# Communication_sheet.net
KiCad netlist of a schematic drawn in Altium Designer
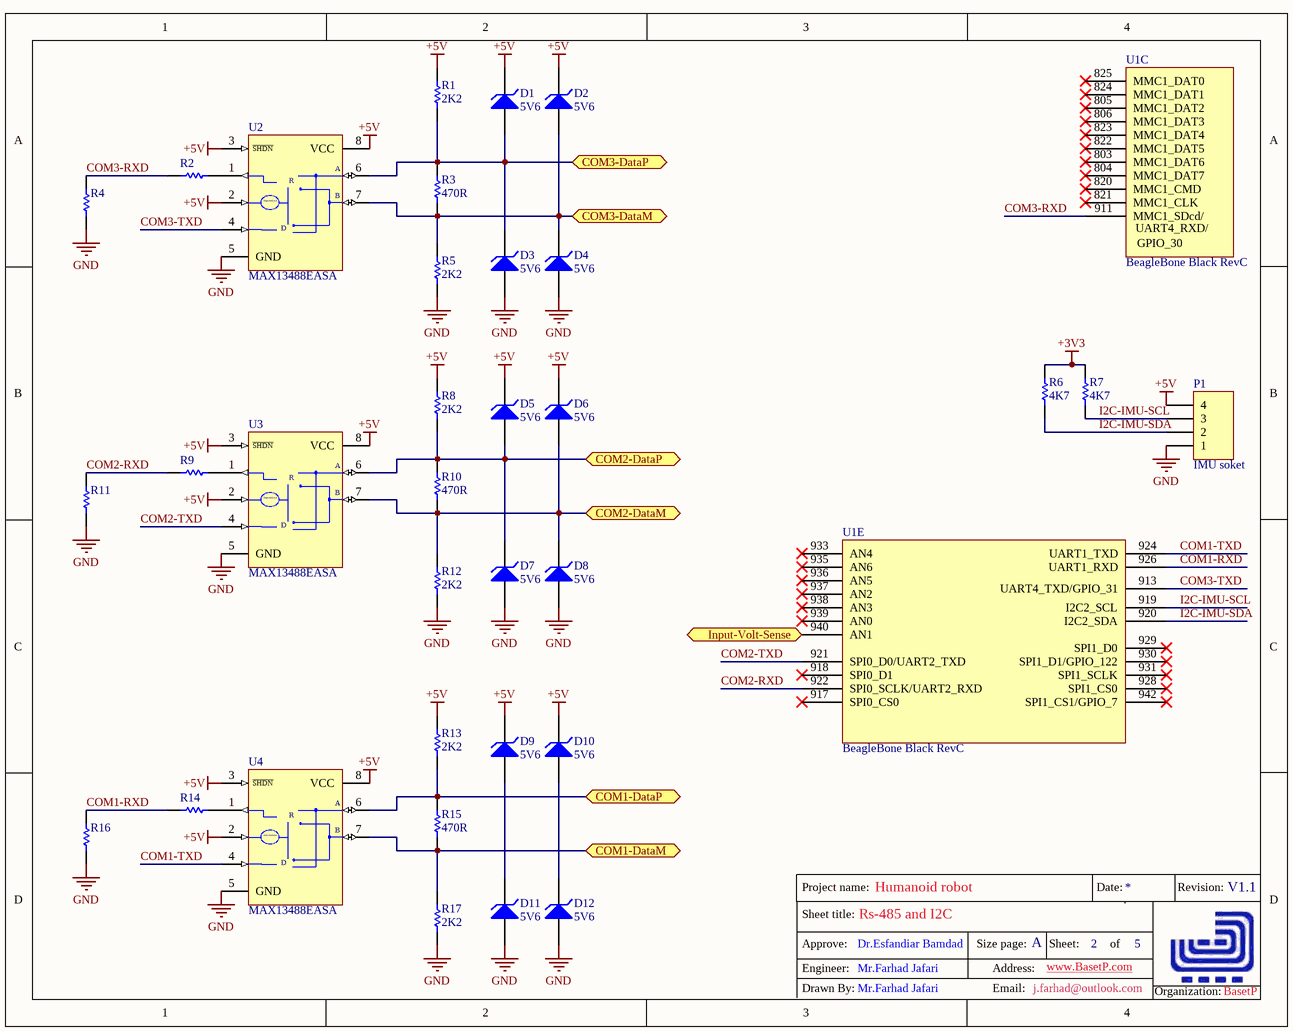
[diagram p0: Communication sheet.SchDoc]

(export (version "E")
  (design (tool "Eeschema 10.0.6"))
  (components
    (comp (ref "D1")
      (value "5V6")
      (footprint "diode-0.4")
      (description "Zener Diode")
      (fields (field (name "PUBLISHER") "Altium Limited"))
      (libsource (lib "Farhad") (part "D Zener"))
    )
    (comp (ref "D2")
      (value "5V6")
      (footprint "diode-0.4")
      (description "Zener Diode")
      (fields (field (name "PUBLISHER") "Altium Limited"))
      (libsource (lib "Farhad") (part "D Zener"))
    )
    (comp (ref "D3")
      (value "5V6")
      (footprint "diode-0.4")
      (description "Zener Diode")
      (fields (field (name "PUBLISHER") "Altium Limited"))
      (libsource (lib "Farhad") (part "D Zener"))
    )
    (comp (ref "D4")
      (value "5V6")
      (footprint "diode-0.4")
      (description "Zener Diode")
      (fields (field (name "PUBLISHER") "Altium Limited"))
      (libsource (lib "Farhad") (part "D Zener"))
    )
    (comp (ref "D5")
      (value "5V6")
      (footprint "diode-0.4")
      (description "Zener Diode")
      (fields (field (name "PUBLISHER") "Altium Limited"))
      (libsource (lib "Farhad") (part "D Zener"))
    )
    (comp (ref "D6")
      (value "5V6")
      (footprint "diode-0.4")
      (description "Zener Diode")
      (fields (field (name "PUBLISHER") "Altium Limited"))
      (libsource (lib "Farhad") (part "D Zener"))
    )
    (comp (ref "D7")
      (value "5V6")
      (footprint "diode-0.4")
      (description "Zener Diode")
      (fields (field (name "PUBLISHER") "Altium Limited"))
      (libsource (lib "Farhad") (part "D Zener"))
    )
    (comp (ref "D8")
      (value "5V6")
      (footprint "diode-0.4")
      (description "Zener Diode")
      (fields (field (name "PUBLISHER") "Altium Limited"))
      (libsource (lib "Farhad") (part "D Zener"))
    )
    (comp (ref "D9")
      (value "5V6")
      (footprint "diode-0.4")
      (description "Zener Diode")
      (fields (field (name "PUBLISHER") "Altium Limited"))
      (libsource (lib "Farhad") (part "D Zener"))
    )
    (comp (ref "D10")
      (value "5V6")
      (footprint "diode-0.4")
      (description "Zener Diode")
      (fields (field (name "PUBLISHER") "Altium Limited"))
      (libsource (lib "Farhad") (part "D Zener"))
    )
    (comp (ref "D11")
      (value "5V6")
      (footprint "diode-0.4")
      (description "Zener Diode")
      (fields (field (name "PUBLISHER") "Altium Limited"))
      (libsource (lib "Farhad") (part "D Zener"))
    )
    (comp (ref "D12")
      (value "5V6")
      (footprint "diode-0.4")
      (description "Zener Diode")
      (fields (field (name "PUBLISHER") "Altium Limited"))
      (libsource (lib "Farhad") (part "D Zener"))
    )
    (comp (ref "P1")
      (value "IMU soket")
      (footprint "HDR1X4")
      (description "Header, 4-Pin")
      (fields (field (name "PUBLISHER") "Altium Limited"))
      (libsource (lib "Farhad_Library") (part "Header 4"))
    )
    (comp (ref "R1")
      (value "2K2")
      (footprint "6-0805")
      (fields (field (name "PUBLISHER") "Altium Limited"))
      (libsource (lib "Panasonic Resistor") (part "ERJ6RS"))
    )
    (comp (ref "R2")
      (value "620")
      (footprint "6-0805")
      (fields (field (name "PUBLISHER") "Altium Limited"))
      (libsource (lib "Panasonic Resistor") (part "ERJ6RS"))
    )
    (comp (ref "R3")
      (value "470R")
      (footprint "6-0805")
      (fields (field (name "PUBLISHER") "Altium Limited"))
      (libsource (lib "Panasonic Resistor") (part "ERJ6RS"))
    )
    (comp (ref "R4")
      (value "1K")
      (footprint "6-0805")
      (fields (field (name "PUBLISHER") "Altium Limited"))
      (libsource (lib "Panasonic Resistor") (part "ERJ6RS"))
    )
    (comp (ref "R5")
      (value "2K2")
      (footprint "6-0805")
      (fields (field (name "PUBLISHER") "Altium Limited"))
      (libsource (lib "Panasonic Resistor") (part "ERJ6RS"))
    )
    (comp (ref "R6")
      (value "4K7")
      (footprint "6-0805")
      (fields (field (name "PUBLISHER") "Altium Limited"))
      (libsource (lib "Panasonic Resistor") (part "ERJ6RS"))
    )
    (comp (ref "R7")
      (value "4K7")
      (footprint "6-0805")
      (fields (field (name "PUBLISHER") "Altium Limited"))
      (libsource (lib "Panasonic Resistor") (part "ERJ6RS"))
    )
    (comp (ref "R8")
      (value "2K2")
      (footprint "6-0805")
      (fields (field (name "PUBLISHER") "Altium Limited"))
      (libsource (lib "Panasonic Resistor") (part "ERJ6RS"))
    )
    (comp (ref "R9")
      (value "680R")
      (footprint "6-0805")
      (fields (field (name "PUBLISHER") "Altium Limited"))
      (libsource (lib "Panasonic Resistor") (part "ERJ6RS"))
    )
    (comp (ref "R10")
      (value "470R")
      (footprint "6-0805")
      (fields (field (name "PUBLISHER") "Altium Limited"))
      (libsource (lib "Panasonic Resistor") (part "ERJ6RS"))
    )
    (comp (ref "R11")
      (value "1K")
      (footprint "6-0805")
      (fields (field (name "PUBLISHER") "Altium Limited"))
      (libsource (lib "Panasonic Resistor") (part "ERJ6RS"))
    )
    (comp (ref "R12")
      (value "2K2")
      (footprint "6-0805")
      (fields (field (name "PUBLISHER") "Altium Limited"))
      (libsource (lib "Panasonic Resistor") (part "ERJ6RS"))
    )
    (comp (ref "R13")
      (value "2K2")
      (footprint "6-0805")
      (fields (field (name "PUBLISHER") "Altium Limited"))
      (libsource (lib "Panasonic Resistor") (part "ERJ6RS"))
    )
    (comp (ref "R14")
      (value "680R")
      (footprint "6-0805")
      (fields (field (name "PUBLISHER") "Altium Limited"))
      (libsource (lib "Panasonic Resistor") (part "ERJ6RS"))
    )
    (comp (ref "R15")
      (value "470R")
      (footprint "6-0805")
      (fields (field (name "PUBLISHER") "Altium Limited"))
      (libsource (lib "Panasonic Resistor") (part "ERJ6RS"))
    )
    (comp (ref "R16")
      (value "1K")
      (footprint "6-0805")
      (fields (field (name "PUBLISHER") "Altium Limited"))
      (libsource (lib "Panasonic Resistor") (part "ERJ6RS"))
    )
    (comp (ref "R17")
      (value "2K2")
      (footprint "6-0805")
      (fields (field (name "PUBLISHER") "Altium Limited"))
      (libsource (lib "Panasonic Resistor") (part "ERJ6RS"))
    )
    (comp (ref "U1")
      (value "BeagleBone Black RevC")
      (footprint "BBB-C")
      (libsource (lib "Farhad_Library") (part "BeagleBoneBlackRevC"))
    )
    (comp (ref "U2")
      (value "MAX13488EASA")
      (footprint "NSO8_N")
      (description "Low-Power,  RS-485/RS-422 Transceiver, Auto direciton")
      (fields (field (name "PUBLISHER") "Farhad Jafari"))
      (libsource (lib "Farhad_Library") (part "MAX13488EASA"))
    )
    (comp (ref "U3")
      (value "MAX13488EASA")
      (footprint "NSO8_N")
      (description "Low-Power,  RS-485/RS-422 Transceiver, Auto direciton")
      (fields (field (name "PUBLISHER") "Farhad Jafari"))
      (libsource (lib "Farhad_Library") (part "MAX13488EASA"))
    )
    (comp (ref "U4")
      (value "MAX13488EASA")
      (footprint "NSO8_N")
      (description "Low-Power,  RS-485/RS-422 Transceiver, Auto direciton")
      (fields (field (name "PUBLISHER") "Farhad Jafari"))
      (libsource (lib "Farhad_Library") (part "MAX13488EASA"))
    )
  )
  (nets
    (net (code "1") (name "+3V3") (class "Default")
      (node (ref "R6") (pin "1") (pinfunction "1_1") (pintype "passive"))
      (node (ref "R7") (pin "1") (pinfunction "1_1") (pintype "passive"))
    )
    (net (code "2") (name "+5V") (class "Default")
      (node (ref "D1") (pin "2") (pinfunction "K_2") (pintype "passive"))
      (node (ref "D10") (pin "2") (pinfunction "K_2") (pintype "passive"))
      (node (ref "D2") (pin "2") (pinfunction "K_2") (pintype "passive"))
      (node (ref "D5") (pin "2") (pinfunction "K_2") (pintype "passive"))
      (node (ref "D6") (pin "2") (pinfunction "K_2") (pintype "passive"))
      (node (ref "D9") (pin "2") (pinfunction "K_2") (pintype "passive"))
      (node (ref "P1") (pin "4") (pinfunction "4_4") (pintype "passive"))
      (node (ref "R1") (pin "1") (pinfunction "1_1") (pintype "passive"))
      (node (ref "R13") (pin "1") (pinfunction "1_1") (pintype "passive"))
      (node (ref "R8") (pin "1") (pinfunction "1_1") (pintype "passive"))
      (node (ref "U2") (pin "2") (pinfunction "~{RE}_2") (pintype "input"))
      (node (ref "U2") (pin "3") (pinfunction "~{SHDN}_3") (pintype "input"))
      (node (ref "U2") (pin "8") (pinfunction "VCC_8") (pintype "power_in"))
      (node (ref "U3") (pin "2") (pinfunction "~{RE}_2") (pintype "input"))
      (node (ref "U3") (pin "3") (pinfunction "~{SHDN}_3") (pintype "input"))
      (node (ref "U3") (pin "8") (pinfunction "VCC_8") (pintype "power_in"))
      (node (ref "U4") (pin "2") (pinfunction "~{RE}_2") (pintype "input"))
      (node (ref "U4") (pin "3") (pinfunction "~{SHDN}_3") (pintype "input"))
      (node (ref "U4") (pin "8") (pinfunction "VCC_8") (pintype "power_in"))
    )
    (net (code "3") (name "/COM1-DataM") (class "Default")
      (node (ref "R15") (pin "2") (pinfunction "2_2") (pintype "passive"))
      (node (ref "R17") (pin "1") (pinfunction "1_1") (pintype "passive"))
      (node (ref "U4") (pin "7") (pinfunction "B_7") (pintype "bidirectional"))
    )
    (net (code "4") (name "/COM1-DataP") (class "Default")
      (node (ref "R13") (pin "2") (pinfunction "2_2") (pintype "passive"))
      (node (ref "R15") (pin "1") (pinfunction "1_1") (pintype "passive"))
      (node (ref "U4") (pin "6") (pinfunction "A_6") (pintype "bidirectional"))
    )
    (net (code "5") (name "/COM1-RXD") (class "Default")
      (node (ref "R14") (pin "1") (pinfunction "1_1") (pintype "passive"))
      (node (ref "R16") (pin "2") (pinfunction "2_2") (pintype "passive"))
      (node (ref "U1") (pin "926") (pinfunction "UART1_RXD_926") (pintype "passive"))
    )
    (net (code "6") (name "/COM1-TXD") (class "Default")
      (node (ref "U1") (pin "924") (pinfunction "UART1_TXD_924") (pintype "passive"))
      (node (ref "U4") (pin "4") (pinfunction "DI_4") (pintype "input"))
    )
    (net (code "7") (name "/COM2-DataM") (class "Default")
      (node (ref "D6") (pin "1") (pinfunction "A_1") (pintype "passive"))
      (node (ref "D8") (pin "2") (pinfunction "K_2") (pintype "passive"))
      (node (ref "R10") (pin "2") (pinfunction "2_2") (pintype "passive"))
      (node (ref "R12") (pin "1") (pinfunction "1_1") (pintype "passive"))
      (node (ref "U3") (pin "7") (pinfunction "B_7") (pintype "bidirectional"))
    )
    (net (code "8") (name "/COM2-DataP") (class "Default")
      (node (ref "D5") (pin "1") (pinfunction "A_1") (pintype "passive"))
      (node (ref "D7") (pin "2") (pinfunction "K_2") (pintype "passive"))
      (node (ref "R10") (pin "1") (pinfunction "1_1") (pintype "passive"))
      (node (ref "R8") (pin "2") (pinfunction "2_2") (pintype "passive"))
      (node (ref "U3") (pin "6") (pinfunction "A_6") (pintype "bidirectional"))
    )
    (net (code "9") (name "/COM2-RXD") (class "Default")
      (node (ref "R11") (pin "1") (pinfunction "1_1") (pintype "passive"))
      (node (ref "R9") (pin "2") (pinfunction "2_2") (pintype "passive"))
      (node (ref "U1") (pin "922") (pinfunction "SPI0_SCLK/UART2_RXD_922") (pintype "passive"))
    )
    (net (code "10") (name "/COM2-TXD") (class "Default")
      (node (ref "U1") (pin "921") (pinfunction "SPI0_D0/UART2_TXD_921") (pintype "passive"))
      (node (ref "U3") (pin "4") (pinfunction "DI_4") (pintype "input"))
    )
    (net (code "11") (name "/COM3-DataM") (class "Default")
      (node (ref "D2") (pin "1") (pinfunction "A_1") (pintype "passive"))
      (node (ref "D4") (pin "2") (pinfunction "K_2") (pintype "passive"))
      (node (ref "R3") (pin "2") (pinfunction "2_2") (pintype "passive"))
      (node (ref "R5") (pin "1") (pinfunction "1_1") (pintype "passive"))
      (node (ref "U2") (pin "7") (pinfunction "B_7") (pintype "bidirectional"))
    )
    (net (code "12") (name "/COM3-DataP") (class "Default")
      (node (ref "D1") (pin "1") (pinfunction "A_1") (pintype "passive"))
      (node (ref "D3") (pin "2") (pinfunction "K_2") (pintype "passive"))
      (node (ref "R1") (pin "2") (pinfunction "2_2") (pintype "passive"))
      (node (ref "R3") (pin "1") (pinfunction "1_1") (pintype "passive"))
      (node (ref "U2") (pin "6") (pinfunction "A_6") (pintype "bidirectional"))
    )
    (net (code "13") (name "/COM3-RXD") (class "Default")
      (node (ref "R2") (pin "1") (pinfunction "1_1") (pintype "passive"))
      (node (ref "R4") (pin "2") (pinfunction "2_2") (pintype "passive"))
      (node (ref "U1") (pin "911") (pinfunction "MMC1_SDcd/_911") (pintype "passive"))
    )
    (net (code "14") (name "/COM3-TXD") (class "Default")
      (node (ref "U1") (pin "913") (pinfunction "UART4_TXD/GPIO_31_913") (pintype "passive"))
      (node (ref "U2") (pin "4") (pinfunction "DI_4") (pintype "input"))
    )
    (net (code "15") (name "/I2C-IMU-SCL") (class "Default")
      (node (ref "P1") (pin "3") (pinfunction "3_3") (pintype "passive"))
      (node (ref "R7") (pin "2") (pinfunction "2_2") (pintype "passive"))
      (node (ref "U1") (pin "919") (pinfunction "I2C2_SCL_919") (pintype "passive"))
    )
    (net (code "16") (name "/I2C-IMU-SDA") (class "Default")
      (node (ref "P1") (pin "2") (pinfunction "2_2") (pintype "passive"))
      (node (ref "R6") (pin "2") (pinfunction "2_2") (pintype "passive"))
      (node (ref "U1") (pin "920") (pinfunction "I2C2_SDA_920") (pintype "passive"))
    )
    (net (code "17") (name "/Input-Volt-Sense") (class "Default")
      (node (ref "U1") (pin "940") (pinfunction "AN1_940") (pintype "passive"))
    )
    (net (code "18") (name "GND") (class "Default")
      (node (ref "D11") (pin "1") (pinfunction "A_1") (pintype "passive"))
      (node (ref "D12") (pin "1") (pinfunction "A_1") (pintype "passive"))
      (node (ref "D3") (pin "1") (pinfunction "A_1") (pintype "passive"))
      (node (ref "D4") (pin "1") (pinfunction "A_1") (pintype "passive"))
      (node (ref "D7") (pin "1") (pinfunction "A_1") (pintype "passive"))
      (node (ref "D8") (pin "1") (pinfunction "A_1") (pintype "passive"))
      (node (ref "P1") (pin "1") (pinfunction "1_1") (pintype "passive"))
      (node (ref "R11") (pin "2") (pinfunction "2_2") (pintype "passive"))
      (node (ref "R12") (pin "2") (pinfunction "2_2") (pintype "passive"))
      (node (ref "R16") (pin "1") (pinfunction "1_1") (pintype "passive"))
      (node (ref "R17") (pin "2") (pinfunction "2_2") (pintype "passive"))
      (node (ref "R4") (pin "1") (pinfunction "1_1") (pintype "passive"))
      (node (ref "R5") (pin "2") (pinfunction "2_2") (pintype "passive"))
      (node (ref "U2") (pin "5") (pinfunction "GND_5") (pintype "power_in"))
      (node (ref "U3") (pin "5") (pinfunction "GND_5") (pintype "power_in"))
      (node (ref "U4") (pin "5") (pinfunction "GND_5") (pintype "power_in"))
    )
    (net (code "19") (name "Net-(D10-A)") (class "Default")
      (node (ref "D10") (pin "1") (pinfunction "A_1") (pintype "passive"))
      (node (ref "D12") (pin "2") (pinfunction "K_2") (pintype "passive"))
    )
    (net (code "20") (name "Net-(D11-K)") (class "Default")
      (node (ref "D11") (pin "2") (pinfunction "K_2") (pintype "passive"))
      (node (ref "D9") (pin "1") (pinfunction "A_1") (pintype "passive"))
    )
    (net (code "21") (name "Net-(U2-RO)") (class "Default")
      (node (ref "R2") (pin "2") (pinfunction "2_2") (pintype "passive"))
      (node (ref "U2") (pin "1") (pinfunction "RO_1") (pintype "output"))
    )
    (net (code "22") (name "Net-(U3-RO)") (class "Default")
      (node (ref "R9") (pin "1") (pinfunction "1_1") (pintype "passive"))
      (node (ref "U3") (pin "1") (pinfunction "RO_1") (pintype "output"))
    )
    (net (code "23") (name "Net-(U4-RO)") (class "Default")
      (node (ref "R14") (pin "2") (pinfunction "2_2") (pintype "passive"))
      (node (ref "U4") (pin "1") (pinfunction "RO_1") (pintype "output"))
    )
    (net (code "24") (name "unconnected-(U1C-MMC1_CLK-Pad821)") (class "Default")
      (node (ref "U1") (pin "821") (pinfunction "MMC1_CLK_821") (pintype "passive+no_connect"))
    )
    (net (code "25") (name "unconnected-(U1C-MMC1_CMD-Pad820)") (class "Default")
      (node (ref "U1") (pin "820") (pinfunction "MMC1_CMD_820") (pintype "passive+no_connect"))
    )
    (net (code "26") (name "unconnected-(U1C-MMC1_DAT0-Pad825)") (class "Default")
      (node (ref "U1") (pin "825") (pinfunction "MMC1_DAT0_825") (pintype "passive+no_connect"))
    )
    (net (code "27") (name "unconnected-(U1C-MMC1_DAT1-Pad824)") (class "Default")
      (node (ref "U1") (pin "824") (pinfunction "MMC1_DAT1_824") (pintype "passive+no_connect"))
    )
    (net (code "28") (name "unconnected-(U1C-MMC1_DAT2-Pad805)") (class "Default")
      (node (ref "U1") (pin "805") (pinfunction "MMC1_DAT2_805") (pintype "passive+no_connect"))
    )
    (net (code "29") (name "unconnected-(U1C-MMC1_DAT3-Pad806)") (class "Default")
      (node (ref "U1") (pin "806") (pinfunction "MMC1_DAT3_806") (pintype "passive+no_connect"))
    )
    (net (code "30") (name "unconnected-(U1C-MMC1_DAT4-Pad823)") (class "Default")
      (node (ref "U1") (pin "823") (pinfunction "MMC1_DAT4_823") (pintype "passive+no_connect"))
    )
    (net (code "31") (name "unconnected-(U1C-MMC1_DAT5-Pad822)") (class "Default")
      (node (ref "U1") (pin "822") (pinfunction "MMC1_DAT5_822") (pintype "passive+no_connect"))
    )
    (net (code "32") (name "unconnected-(U1C-MMC1_DAT6-Pad803)") (class "Default")
      (node (ref "U1") (pin "803") (pinfunction "MMC1_DAT6_803") (pintype "passive+no_connect"))
    )
    (net (code "33") (name "unconnected-(U1C-MMC1_DAT7-Pad804)") (class "Default")
      (node (ref "U1") (pin "804") (pinfunction "MMC1_DAT7_804") (pintype "passive+no_connect"))
    )
    (net (code "34") (name "unconnected-(U1E-AN0-Pad939)") (class "Default")
      (node (ref "U1") (pin "939") (pinfunction "AN0_939") (pintype "passive+no_connect"))
    )
    (net (code "35") (name "unconnected-(U1E-AN2-Pad937)") (class "Default")
      (node (ref "U1") (pin "937") (pinfunction "AN2_937") (pintype "passive+no_connect"))
    )
    (net (code "36") (name "unconnected-(U1E-AN3-Pad938)") (class "Default")
      (node (ref "U1") (pin "938") (pinfunction "AN3_938") (pintype "passive+no_connect"))
    )
    (net (code "37") (name "unconnected-(U1E-AN4-Pad933)") (class "Default")
      (node (ref "U1") (pin "933") (pinfunction "AN4_933") (pintype "passive+no_connect"))
    )
    (net (code "38") (name "unconnected-(U1E-AN5-Pad936)") (class "Default")
      (node (ref "U1") (pin "936") (pinfunction "AN5_936") (pintype "passive+no_connect"))
    )
    (net (code "39") (name "unconnected-(U1E-AN6-Pad935)") (class "Default")
      (node (ref "U1") (pin "935") (pinfunction "AN6_935") (pintype "passive+no_connect"))
    )
    (net (code "40") (name "unconnected-(U1E-SPI0_CS0-Pad917)") (class "Default")
      (node (ref "U1") (pin "917") (pinfunction "SPI0_CS0_917") (pintype "passive+no_connect"))
    )
    (net (code "41") (name "unconnected-(U1E-SPI0_D1-Pad918)") (class "Default")
      (node (ref "U1") (pin "918") (pinfunction "SPI0_D1_918") (pintype "passive+no_connect"))
    )
    (net (code "42") (name "unconnected-(U1E-SPI1_CS0-Pad928)") (class "Default")
      (node (ref "U1") (pin "928") (pinfunction "SPI1_CS0_928") (pintype "passive+no_connect"))
    )
    (net (code "43") (name "unconnected-(U1E-SPI1_CS1{slash}GPIO_7-Pad942)") (class "Default")
      (node (ref "U1") (pin "942") (pinfunction "SPI1_CS1/GPIO_7_942") (pintype "passive+no_connect"))
    )
    (net (code "44") (name "unconnected-(U1E-SPI1_D0-Pad929)") (class "Default")
      (node (ref "U1") (pin "929") (pinfunction "SPI1_D0_929") (pintype "passive+no_connect"))
    )
    (net (code "45") (name "unconnected-(U1E-SPI1_D1{slash}GPIO_122-Pad930)") (class "Default")
      (node (ref "U1") (pin "930") (pinfunction "SPI1_D1/GPIO_122_930") (pintype "passive+no_connect"))
    )
    (net (code "46") (name "unconnected-(U1E-SPI1_SCLK-Pad931)") (class "Default")
      (node (ref "U1") (pin "931") (pinfunction "SPI1_SCLK_931") (pintype "passive+no_connect"))
    )
  )
)
